# IF1001.net
KiCad netlist of a schematic drawn in Altium Designer
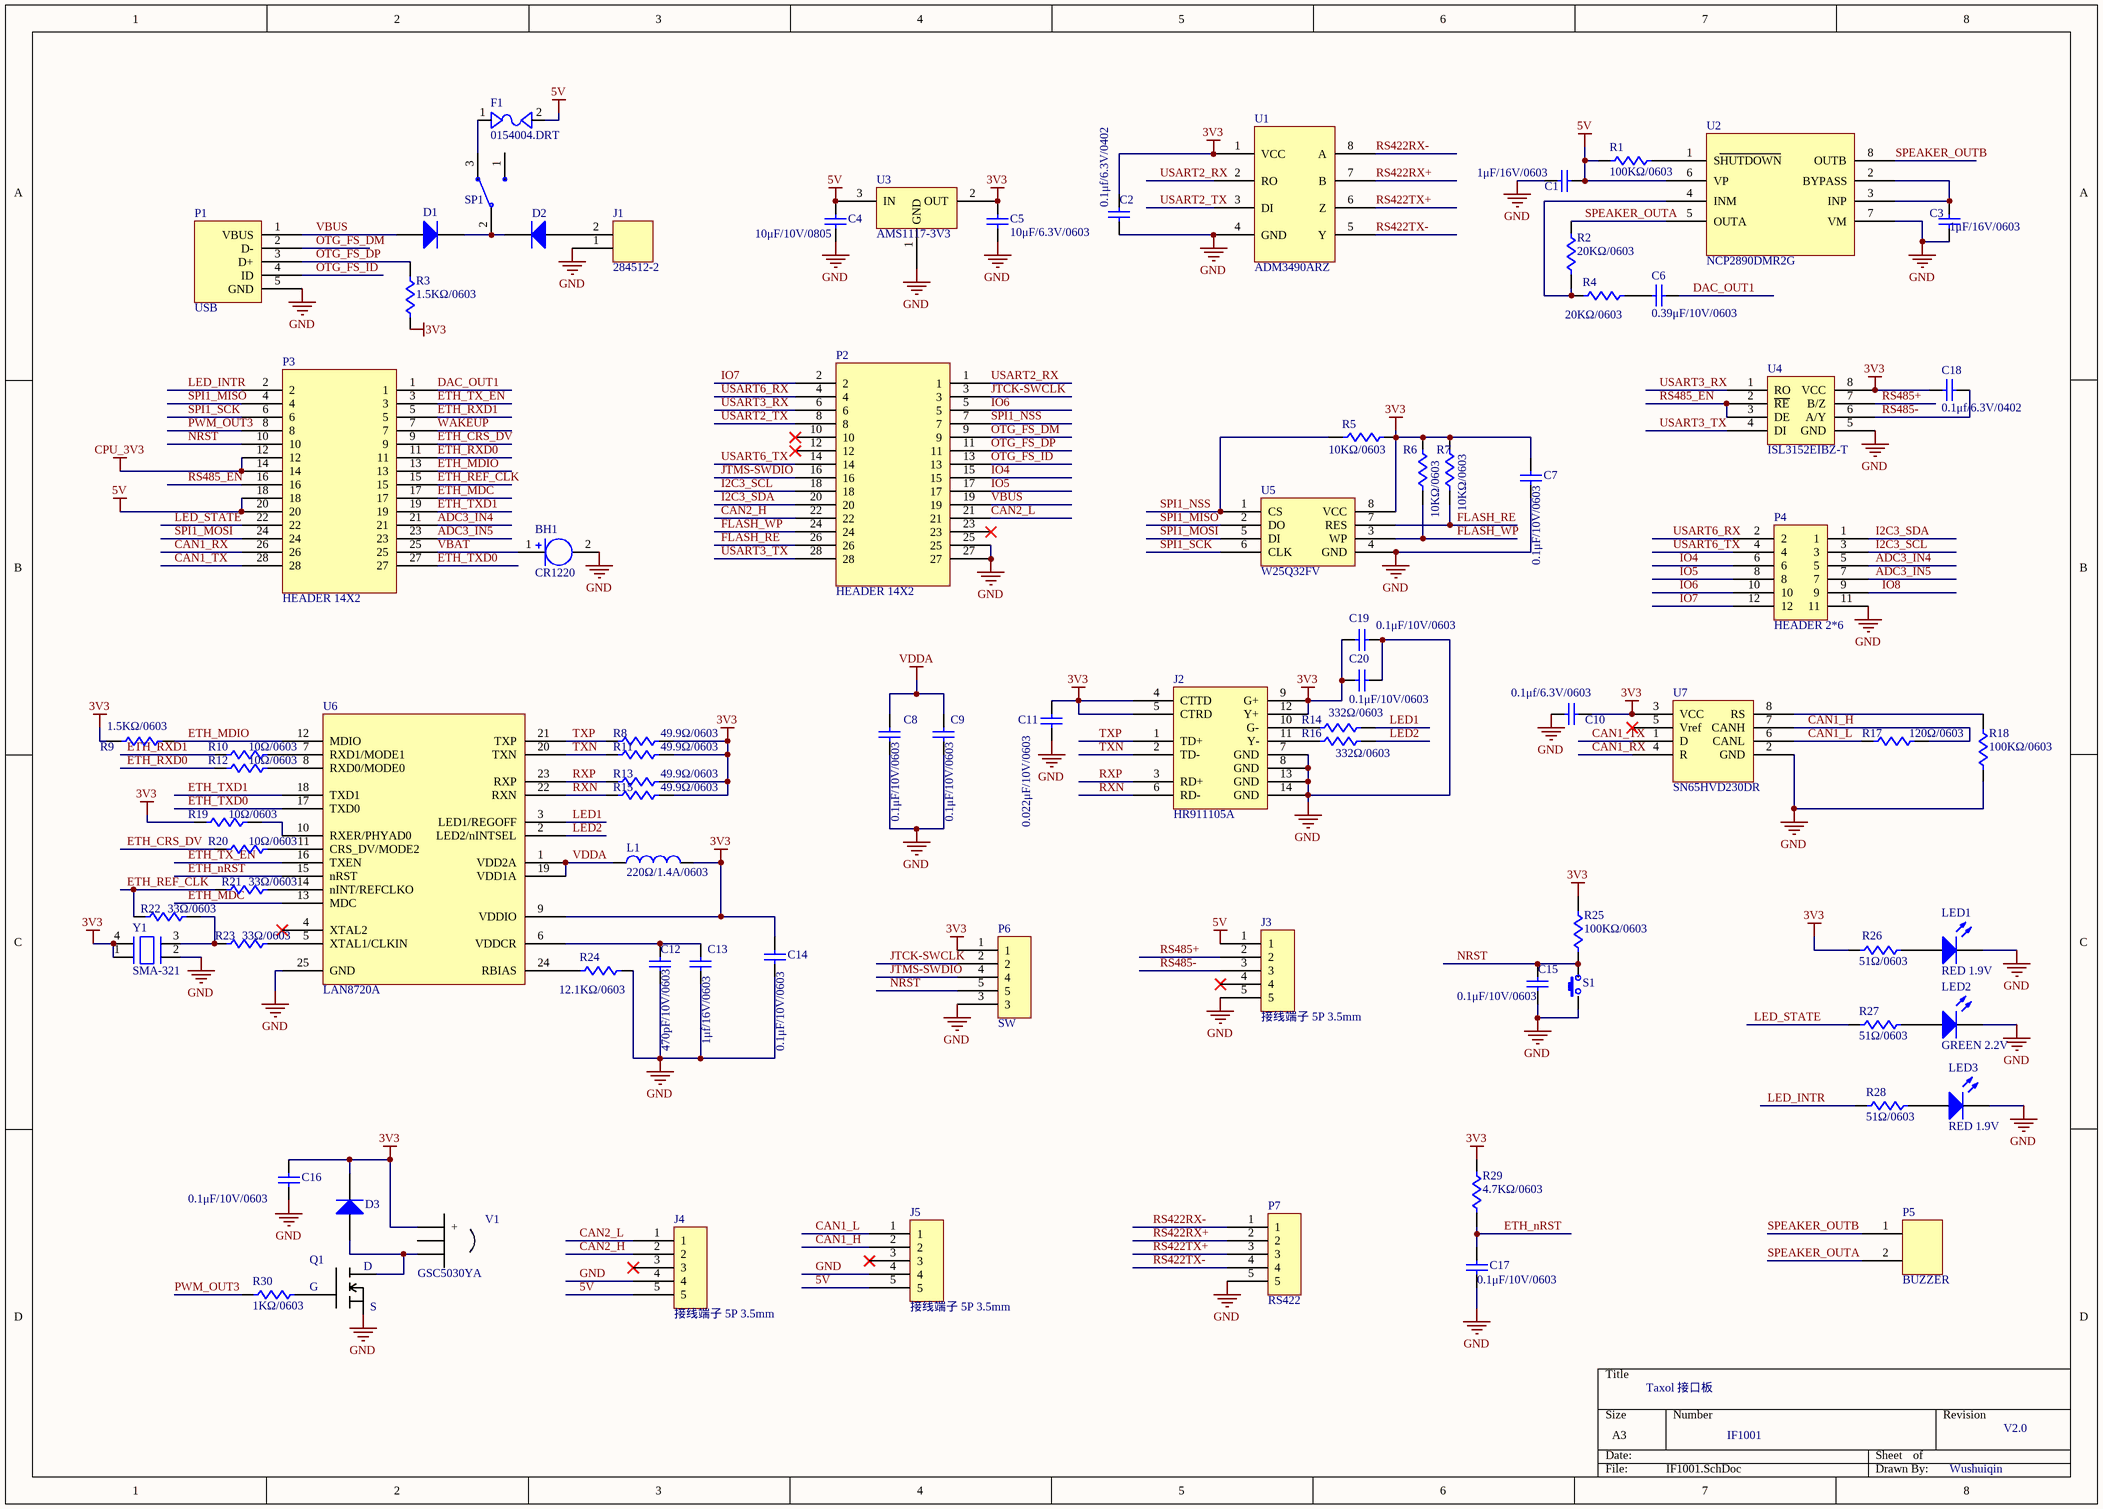
[diagram p0: IF1001.SchDoc]

(export (version "E")
  (design (tool "Eeschema 10.0.6"))
  (components
    (comp (ref "BH1")
      (value "CR1220")
      (footprint "CR1220")
      (fields (field (name "MANUFACTURER") "深圳市吉特雅电子有限公司"))
      (libsource (lib "IF1001") (part "CR1220电池座"))
    )
    (comp (ref "C1")
      (value "1μF/16V/0603")
      (footprint "CAPACITOR_0603")
      (fields (field (name "MANUFACTURER") "TDK"))
      (libsource (lib "Taxol") (part "CAPACITOR_0603"))
    )
    (comp (ref "C2")
      (value "0.1μf/6.3V/0402")
      (footprint "CAPACITOR_0402")
      (fields (field (name "MANUFACTURER") "TDK"))
      (libsource (lib "Taxol") (part "CAPACITOR_0603"))
    )
    (comp (ref "C3")
      (value "1μF/16V/0603")
      (footprint "CAPACITOR_0603")
      (fields (field (name "MANUFACTURER") "TDK"))
      (libsource (lib "Taxol") (part "CAPACITOR_0603"))
    )
    (comp (ref "C4")
      (value "10μF/10V/0805")
      (footprint "CAPACITOR_0805")
      (description "陶瓷电容")
      (fields (field (name "MANUFACTURER") "TDK"))
      (libsource (lib "IF1005") (part "CAP0805 UP"))
    )
    (comp (ref "C5")
      (value "10μF/6.3V/0603")
      (footprint "CAPACITOR_0603")
      (description "陶瓷电容")
      (fields (field (name "MANUFACTURER") "TDK"))
      (libsource (lib "IF1005") (part "CAP0603 UP"))
    )
    (comp (ref "C6")
      (value "0.39μF/10V/0603")
      (footprint "CAPACITOR_0603")
      (fields (field (name "MANUFACTURER") "kemet"))
      (libsource (lib "Taxol") (part "CAPACITOR_0603"))
    )
    (comp (ref "C7")
      (value "0.1μF/10V/0603")
      (footprint "CAPACITOR_0603")
      (fields (field (name "MANUFACTURER") "Vishay"))
      (libsource (lib "Taxol") (part "CAPACITOR_0603"))
    )
    (comp (ref "C8")
      (value "0.1μF/10V/0603")
      (footprint "CAPACITOR_0603")
      (fields (field (name "MANUFACTURER") "Vishay"))
      (libsource (lib "Taxol") (part "CAPACITOR_0603"))
    )
    (comp (ref "C9")
      (value "0.1μF/10V/0603")
      (footprint "CAPACITOR_0603")
      (fields (field (name "MANUFACTURER") "Vishay"))
      (libsource (lib "Taxol") (part "CAPACITOR_0603"))
    )
    (comp (ref "C10")
      (value "0.1μf/6.3V/0603")
      (footprint "CAPACITOR_0603")
      (fields (field (name "MANUFACTURER") "TDK"))
      (libsource (lib "Taxol") (part "CAPACITOR_0603"))
    )
    (comp (ref "C11")
      (value "0.022μF/10V/0603")
      (footprint "CAPACITOR_0603")
      (fields (field (name "MANUFACTURER") "Vishay"))
      (libsource (lib "IF1001") (part "CAPACITOR_0603"))
    )
    (comp (ref "C12")
      (value "470pF/10V/0603")
      (footprint "CAPACITOR_0603")
      (fields (field (name "MANUFACTURER") "Vishay"))
      (libsource (lib "IF1001") (part "CAPACITOR_0603"))
    )
    (comp (ref "C13")
      (value "1μf/16V/0603")
      (footprint "CAPACITOR_0603")
      (fields (field (name "MANUFACTURER") "TDK"))
      (libsource (lib "Taxol") (part "CAPACITOR_0603"))
    )
    (comp (ref "C14")
      (value "0.1μF/10V/0603")
      (footprint "CAPACITOR_0603")
      (fields (field (name "MANUFACTURER") "Vishay"))
      (libsource (lib "Taxol") (part "CAPACITOR_0603"))
    )
    (comp (ref "C15")
      (value "0.1μF/10V/0603")
      (footprint "CAPACITOR_0603")
      (fields (field (name "MANUFACTURER") "Vishay"))
      (libsource (lib "Taxol") (part "CAPACITOR_0603"))
    )
    (comp (ref "C16")
      (value "0.1μF/10V/0603")
      (footprint "CAPACITOR_0603")
      (fields (field (name "MANUFACTURER") "Vishay"))
      (libsource (lib "Taxol") (part "CAPACITOR_0603"))
    )
    (comp (ref "C17")
      (value "0.1μF/10V/0603")
      (footprint "CAPACITOR_0603")
      (fields (field (name "MANUFACTURER") "Vishay"))
      (libsource (lib "Taxol") (part "CAPACITOR_0603"))
    )
    (comp (ref "C18")
      (value "0.1μf/6.3V/0402")
      (footprint "CAPACITOR_0402")
      (fields (field (name "MANUFACTURER") "TDK"))
      (libsource (lib "Taxol") (part "CAPACITOR_0603"))
    )
    (comp (ref "C19")
      (value "0.1μF/10V/0603")
      (footprint "CAPACITOR_0603")
      (fields (field (name "MANUFACTURER") "Vishay"))
      (libsource (lib "Taxol") (part "CAPACITOR_0603"))
    )
    (comp (ref "C20")
      (value "0.1μF/10V/0603")
      (footprint "CAPACITOR_0603")
      (fields (field (name "MANUFACTURER") "Vishay"))
      (libsource (lib "Taxol") (part "CAPACITOR_0603"))
    )
    (comp (ref "D1")
      (value "BAT60JFILM")
      (footprint "BAT60JFILM")
      (fields (field (name "MANUFACTURER") "ST"))
      (libsource (lib "IF1001") (part "BAT60JFILM"))
    )
    (comp (ref "D2")
      (value "BAT60JFILM")
      (footprint "BAT60JFILM")
      (fields (field (name "MANUFACTURER") "ST"))
      (libsource (lib "IF1001") (part "BAT60JFILM"))
    )
    (comp (ref "D3")
      (value "PMEG2010AEB")
      (footprint "PMEG2010AEB_SOD523")
      (fields (field (name "MANUFACTURER") "NXP"))
      (libsource (lib "IF1001") (part "PMEG2010AEB"))
    )
    (comp (ref "F1")
      (value "0154004.DRT")
      (footprint "FUSE1808")
      (description "保险丝")
      (fields (field (name "MANUFACTURER") "Littlefuse"))
      (libsource (lib "IF1001") (part "F_4A"))
    )
    (comp (ref "J1")
      (value "284512-2")
      (footprint "284512-2")
      (description "间距3.5mm")
      (fields (field (name "MANUFACTURER") "TE"))
      (libsource (lib "IF1001") (part "接线端子 2P 3.5mm"))
    )
    (comp (ref "J2")
      (value "HR911105A")
      (footprint "HR911105A")
      (fields (field (name "MANUFACTURER") "深圳市诚亨泰科技有限公司"))
      (libsource (lib "IF1001") (part "HR911105A"))
    )
    (comp (ref "J3")
      (value "接线端子 5P 3.5mm")
      (footprint "接线端子5P 3.5mm")
      (fields (field (name "MANUFACTURER") "KEFA"))
      (libsource (lib "IF1001") (part "接线端子 5P 3.5mm"))
    )
    (comp (ref "J4")
      (value "接线端子 5P 3.5mm")
      (footprint "接线端子5P 3.5mm")
      (fields (field (name "MANUFACTURER") "KEFA"))
      (libsource (lib "IF1001") (part "接线端子 5P 3.5mm"))
    )
    (comp (ref "J5")
      (value "接线端子 5P 3.5mm")
      (footprint "接线端子5P 3.5mm")
      (fields (field (name "MANUFACTURER") "KEFA"))
      (libsource (lib "IF1001") (part "接线端子 5P 3.5mm"))
    )
    (comp (ref "L1")
      (value "220Ω/1.4A/0603")
      (footprint "LNDUCTOR 0603")
      (description "磁珠")
      (fields (field (name "MANUFACTURER") "Murata"))
      (libsource (lib "IF1001") (part "BLM18PG221SN1D"))
    )
    (comp (ref "LED1")
      (value "RED 1.9V")
      (footprint "LED")
      (description "LED_G")
      (fields (field (name "MANUFACTURER") "OSRAM"))
      (libsource (lib "IF1001") (part "LED"))
    )
    (comp (ref "LED2")
      (value "GREEN 2.2V")
      (footprint "LED")
      (description "LED_G")
      (fields (field (name "MANUFACTURER") "OSRAM"))
      (libsource (lib "IF1001") (part "LED"))
    )
    (comp (ref "LED3")
      (value "RED 1.9V")
      (footprint "LED")
      (description "LED_G")
      (fields (field (name "MANUFACTURER") "OSRAM"))
      (libsource (lib "IF1001") (part "LED"))
    )
    (comp (ref "P1")
      (value "USB")
      (footprint "MINI_USB")
      (fields (field (name "MANUFACTURER") "JAE"))
      (libsource (lib "Taxol") (part "Mini_USB"))
    )
    (comp (ref "P2") (value "HEADER 14X2") (footprint "PIN") (libsource (lib "PT1003") (part "PIN_1")))
    (comp (ref "P3") (value "HEADER 14X2") (footprint "PIN") (libsource (lib "PT1003") (part "PIN_1")))
    (comp (ref "P4")
      (value "HEADER 2*6")
      (footprint "HEADER 2*6")
      (libsource (lib "IF1001") (part "HEADER 2*6"))
    )
    (comp (ref "P5") (value "BUZZER") (footprint "HEADER 1*2") (libsource (lib "Taxol") (part "HEADER 1*2")))
    (comp (ref "P6") (value "SW") (footprint "HEADER 1*5") (libsource (lib "Taxol") (part "SW")))
    (comp (ref "P7") (value "RS422") (footprint "HEADER 1*5") (libsource (lib "IF1001") (part "HEADER 1*5")))
    (comp (ref "Q1")
      (value "PMV185XN")
      (footprint "PMV185XN")
      (fields (field (name "MANUFACTURER") "NXP"))
      (libsource (lib "Taxol") (part "MOSFET"))
    )
    (comp (ref "R1")
      (value "100KΩ/0603")
      (footprint "RESSOSTANCE_0603")
      (fields (field (name "MANUFACTURER") "VISHAY"))
      (libsource (lib "Taxol") (part "RESISTANCE"))
    )
    (comp (ref "R2")
      (value "20KΩ/0603")
      (footprint "RESSOSTANCE_0603")
      (fields (field (name "MANUFACTURER") "VISHAY"))
      (libsource (lib "Taxol") (part "RESISTANCE"))
    )
    (comp (ref "R3")
      (value "1.5KΩ/0603")
      (footprint "RESSOSTANCE_0603")
      (fields (field (name "MANUFACTURER") "VISHAY"))
      (libsource (lib "Taxol") (part "RESISTANCE"))
    )
    (comp (ref "R4")
      (value "20KΩ/0603")
      (footprint "RESSOSTANCE_0603")
      (fields (field (name "MANUFACTURER") "VISHAY"))
      (libsource (lib "Taxol") (part "RESISTANCE"))
    )
    (comp (ref "R5")
      (value "10KΩ/0603")
      (footprint "RESSOSTANCE_0603")
      (fields (field (name "MANUFACTURER") "KOA Speer"))
      (libsource (lib "IF1001") (part "RESISTANCE"))
    )
    (comp (ref "R6")
      (value "10KΩ/0603")
      (footprint "RESSOSTANCE_0603")
      (fields (field (name "MANUFACTURER") "KOA Speer"))
      (libsource (lib "IF1001") (part "RESISTANCE"))
    )
    (comp (ref "R7")
      (value "10KΩ/0603")
      (footprint "RESSOSTANCE_0603")
      (fields (field (name "MANUFACTURER") "KOA Speer"))
      (libsource (lib "IF1001") (part "RESISTANCE"))
    )
    (comp (ref "R8")
      (value "49.9Ω/0603")
      (footprint "RESSOSTANCE_0603")
      (fields (field (name "MANUFACTURER") "Vishay"))
      (libsource (lib "IF1001") (part "RESISTANCE"))
    )
    (comp (ref "R9")
      (value "1.5KΩ/0603")
      (footprint "RESSOSTANCE_0603")
      (fields (field (name "MANUFACTURER") "VISHAY"))
      (libsource (lib "Taxol") (part "RESISTANCE"))
    )
    (comp (ref "R10")
      (value "10Ω/0603")
      (footprint "RESSOSTANCE_0603")
      (fields (field (name "MANUFACTURER") "Vishay"))
      (libsource (lib "IF1001") (part "RESISTANCE"))
    )
    (comp (ref "R11")
      (value "49.9Ω/0603")
      (footprint "RESSOSTANCE_0603")
      (fields (field (name "MANUFACTURER") "Vishay"))
      (libsource (lib "IF1001") (part "RESISTANCE"))
    )
    (comp (ref "R12")
      (value "10Ω/0603")
      (footprint "RESSOSTANCE_0603")
      (fields (field (name "MANUFACTURER") "Vishay"))
      (libsource (lib "IF1001") (part "RESISTANCE"))
    )
    (comp (ref "R13")
      (value "49.9Ω/0603")
      (footprint "RESSOSTANCE_0603")
      (fields (field (name "MANUFACTURER") "Vishay"))
      (libsource (lib "IF1001") (part "RESISTANCE"))
    )
    (comp (ref "R14")
      (value "332Ω/0603")
      (footprint "RESSOSTANCE_0603")
      (fields (field (name "MANUFACTURER") "Vishay"))
      (libsource (lib "IF1001") (part "RESISTANCE"))
    )
    (comp (ref "R15")
      (value "49.9Ω/0603")
      (footprint "RESSOSTANCE_0603")
      (fields (field (name "MANUFACTURER") "Vishay"))
      (libsource (lib "IF1001") (part "RESISTANCE"))
    )
    (comp (ref "R16")
      (value "332Ω/0603")
      (footprint "RESSOSTANCE_0603")
      (fields (field (name "MANUFACTURER") "Vishay"))
      (libsource (lib "IF1001") (part "RESISTANCE"))
    )
    (comp (ref "R17")
      (value "120Ω/0603")
      (footprint "RESSOSTANCE_0603")
      (fields (field (name "MANUFACTURER") "Vishay"))
      (libsource (lib "PT1003") (part "RESISTANCE"))
    )
    (comp (ref "R18")
      (value "100KΩ/0603")
      (footprint "RESSOSTANCE_0603")
      (fields (field (name "MANUFACTURER") "VISHAY"))
      (libsource (lib "Taxol") (part "RESISTANCE"))
    )
    (comp (ref "R19")
      (value "10Ω/0603")
      (footprint "RESSOSTANCE_0603")
      (fields (field (name "MANUFACTURER") "Vishay"))
      (libsource (lib "IF1001") (part "RESISTANCE"))
    )
    (comp (ref "R20")
      (value "10Ω/0603")
      (footprint "RESSOSTANCE_0603")
      (fields (field (name "MANUFACTURER") "Vishay"))
      (libsource (lib "IF1001") (part "RESISTANCE"))
    )
    (comp (ref "R21")
      (value "33Ω/0603")
      (footprint "RESSOSTANCE_0603")
      (fields (field (name "MANUFACTURER") "Vishay"))
      (libsource (lib "IF1001") (part "RESISTANCE"))
    )
    (comp (ref "R22")
      (value "33Ω/0603")
      (footprint "RESSOSTANCE_0603")
      (fields (field (name "MANUFACTURER") "Vishay"))
      (libsource (lib "IF1001") (part "RESISTANCE"))
    )
    (comp (ref "R23")
      (value "33Ω/0603")
      (footprint "RESSOSTANCE_0603")
      (fields (field (name "MANUFACTURER") "Vishay"))
      (libsource (lib "IF1001") (part "RESISTANCE"))
    )
    (comp (ref "R24")
      (value "12.1KΩ/0603")
      (footprint "RESSOSTANCE_0603")
      (fields (field (name "MANUFACTURER") "Vishay"))
      (libsource (lib "IF1001") (part "RESISTANCE"))
    )
    (comp (ref "R25")
      (value "100KΩ/0603")
      (footprint "RESSOSTANCE_0603")
      (fields (field (name "MANUFACTURER") "VISHAY"))
      (libsource (lib "Taxol") (part "RESISTANCE"))
    )
    (comp (ref "R26")
      (value "51Ω/0603")
      (footprint "RESSOSTANCE_0603")
      (fields (field (name "MANUFACTURER") "Vishay"))
      (libsource (lib "IF1001") (part "RESISTANCE"))
    )
    (comp (ref "R27")
      (value "51Ω/0603")
      (footprint "RESSOSTANCE_0603")
      (fields (field (name "MANUFACTURER") "Vishay"))
      (libsource (lib "IF1001") (part "RESISTANCE"))
    )
    (comp (ref "R28")
      (value "51Ω/0603")
      (footprint "RESSOSTANCE_0603")
      (fields (field (name "MANUFACTURER") "Vishay"))
      (libsource (lib "IF1001") (part "RESISTANCE"))
    )
    (comp (ref "R29")
      (value "4.7KΩ/0603")
      (footprint "RESSOSTANCE_0603")
      (fields (field (name "MANUFACTURER") "Vishay"))
      (libsource (lib "IF1001") (part "RESISTANCE"))
    )
    (comp (ref "R30")
      (value "1KΩ/0603")
      (footprint "RESSOSTANCE_0603")
      (fields (field (name "MANUFACTURER") "VISHAY"))
      (libsource (lib "Taxol") (part "RESISTANCE"))
    )
    (comp (ref "S1")
      (value "K2-1107ST")
      (footprint "SW-侧开")
      (fields (field (name "MANUFACTURER") "韩荣"))
      (libsource (lib "Taxol") (part "SW_PB"))
    )
    (comp (ref "SP1")
      (value "2.00mm 3P SPDT")
      (footprint "SW-STDP")
      (libsource (lib "Taxol") (part "SW_STDP"))
    )
    (comp (ref "U1")
      (value "ADM3490ARZ")
      (footprint "ADM3490")
      (description "RS422")
      (fields (field (name "MANUFACTURER") "ANALOG DEVICES"))
      (libsource (lib "Taxol") (part "ADM3490ARZ"))
    )
    (comp (ref "U2")
      (value "NCP2890DMR2G")
      (footprint "NCP2890")
      (description "AUDIO")
      (fields (field (name "MANUFACTURER") "ON"))
      (libsource (lib "Taxol") (part "NCP2890DMR2G"))
    )
    (comp (ref "U3")
      (value "AMS1117-3V3")
      (footprint "AMS1117-3V3")
      (description "3V3稳压芯片")
      (fields (field (name "MANUFACTURER") "Advanced Monolithic Systems"))
      (libsource (lib "IF1005") (part "AMS1117-3V3"))
    )
    (comp (ref "U4")
      (value "ISL3152EIBZ-T")
      (footprint "ISL3152EIBZ-T")
      (description "RS485接口芯片")
      (fields (field (name "MANUFACTURER") "INTERSIL"))
      (libsource (lib "IF1001") (part "ISL3152EIBZ-T"))
    )
    (comp (ref "U5")
      (value "W25Q32FV")
      (footprint "W25Q32FV")
      (fields (field (name "MANUFACTURER") "华邦电子"))
      (libsource (lib "IF1001") (part "W25Q32FV"))
    )
    (comp (ref "U6")
      (value "LAN8720A")
      (footprint "LAN8720A")
      (fields (field (name "MANUFACTURER") "SMSC"))
      (libsource (lib "IF1001") (part "LAN8720A"))
    )
    (comp (ref "U7")
      (value "SN65HVD230DR")
      (footprint "SN65HVD230")
      (description "CAN")
      (fields (field (name "MANUFACTURER") "TEXAS INSTRUMENTS"))
      (libsource (lib "Taxol") (part "SN65HVD230DR"))
    )
    (comp (ref "V1")
      (value "GSC5030YA")
      (footprint "GSC5030YA-12R4000")
      (fields (field (name "MANUFACTURER") "INGHAI"))
      (libsource (lib "Taxol") (part "BUZZER"))
    )
    (comp (ref "Y1")
      (value "SMA-321")
      (footprint "XO35")
      (description "有源晶振")
      (fields (field (name "MANUFACTURER") "AKER"))
      (libsource (lib "IF1001") (part "SMA-321"))
    )
  )
  (nets
    (net (code "1") (name "/ADC3_IN4") (class "Default")
      (node (ref "P3") (pin "21") (pinfunction "21_21") (pintype "passive"))
      (node (ref "P4") (pin "5") (pinfunction "5_5") (pintype "passive"))
    )
    (net (code "2") (name "/ADC3_IN5") (class "Default")
      (node (ref "P3") (pin "23") (pinfunction "23_23") (pintype "passive"))
      (node (ref "P4") (pin "7") (pinfunction "7_7") (pintype "passive"))
    )
    (net (code "3") (name "/CAN1_H") (class "Default")
      (node (ref "J5") (pin "2") (pinfunction "2_2") (pintype "passive"))
      (node (ref "R17") (pin "2") (pinfunction "2_2") (pintype "passive"))
      (node (ref "U7") (pin "7") (pinfunction "CANH_7") (pintype "passive"))
    )
    (net (code "4") (name "/CAN1_L") (class "Default")
      (node (ref "J5") (pin "1") (pinfunction "1_1") (pintype "passive"))
      (node (ref "R17") (pin "1") (pinfunction "1_1") (pintype "passive"))
      (node (ref "U7") (pin "6") (pinfunction "CANL_6") (pintype "passive"))
    )
    (net (code "5") (name "/CAN1_RX") (class "Default")
      (node (ref "P3") (pin "26") (pinfunction "26_26") (pintype "passive"))
      (node (ref "U7") (pin "4") (pinfunction "R_4") (pintype "passive"))
    )
    (net (code "6") (name "/CAN1_TX") (class "Default")
      (node (ref "P3") (pin "28") (pinfunction "28_28") (pintype "passive"))
      (node (ref "U7") (pin "1") (pinfunction "D_1") (pintype "passive"))
    )
    (net (code "7") (name "/CAN2_H") (class "Default")
      (node (ref "J4") (pin "2") (pinfunction "2_2") (pintype "passive"))
      (node (ref "P2") (pin "22") (pinfunction "22_22") (pintype "passive"))
    )
    (net (code "8") (name "/CAN2_L") (class "Default")
      (node (ref "J4") (pin "1") (pinfunction "1_1") (pintype "passive"))
      (node (ref "P2") (pin "21") (pinfunction "21_21") (pintype "passive"))
    )
    (net (code "9") (name "/DAC_OUT1") (class "Default")
      (node (ref "C6") (pin "2") (pinfunction "2_2") (pintype "passive"))
      (node (ref "P3") (pin "1") (pinfunction "1_1") (pintype "passive"))
    )
    (net (code "10") (name "/ETH_CRS_DV") (class "Default")
      (node (ref "P3") (pin "9") (pinfunction "9_9") (pintype "passive"))
      (node (ref "R20") (pin "1") (pinfunction "1_1") (pintype "passive"))
    )
    (net (code "11") (name "/ETH_MDC") (class "Default")
      (node (ref "P3") (pin "17") (pinfunction "17_17") (pintype "passive"))
      (node (ref "U6") (pin "13") (pinfunction "MDC_13") (pintype "passive"))
    )
    (net (code "12") (name "/ETH_MDIO") (class "Default")
      (node (ref "P3") (pin "13") (pinfunction "13_13") (pintype "passive"))
      (node (ref "R9") (pin "1") (pinfunction "1_1") (pintype "passive"))
      (node (ref "U6") (pin "12") (pinfunction "MDIO_12") (pintype "passive"))
    )
    (net (code "13") (name "/ETH_REF_CLK") (class "Default")
      (node (ref "P3") (pin "15") (pinfunction "15_15") (pintype "passive"))
      (node (ref "R21") (pin "1") (pinfunction "1_1") (pintype "passive"))
      (node (ref "R22") (pin "1") (pinfunction "1_1") (pintype "passive"))
    )
    (net (code "14") (name "/ETH_RXD0") (class "Default")
      (node (ref "P3") (pin "11") (pinfunction "11_11") (pintype "passive"))
      (node (ref "R12") (pin "1") (pinfunction "1_1") (pintype "passive"))
    )
    (net (code "15") (name "/ETH_RXD1") (class "Default")
      (node (ref "P3") (pin "5") (pinfunction "5_5") (pintype "passive"))
      (node (ref "R10") (pin "1") (pinfunction "1_1") (pintype "passive"))
    )
    (net (code "16") (name "/ETH_TXD0") (class "Default")
      (node (ref "P3") (pin "27") (pinfunction "27_27") (pintype "passive"))
      (node (ref "U6") (pin "17") (pinfunction "TXD0_17") (pintype "passive"))
    )
    (net (code "17") (name "/ETH_TXD1") (class "Default")
      (node (ref "P3") (pin "19") (pinfunction "19_19") (pintype "passive"))
      (node (ref "U6") (pin "18") (pinfunction "TXD1_18") (pintype "passive"))
    )
    (net (code "18") (name "/ETH_TX_EN") (class "Default")
      (node (ref "P3") (pin "3") (pinfunction "3_3") (pintype "passive"))
      (node (ref "U6") (pin "16") (pinfunction "TXEN_16") (pintype "passive"))
    )
    (net (code "19") (name "/ETH_nRST") (class "Default")
      (node (ref "C17") (pin "2") (pinfunction "2_2") (pintype "passive"))
      (node (ref "R29") (pin "2") (pinfunction "2_2") (pintype "passive"))
      (node (ref "U6") (pin "15") (pinfunction "nRST_15") (pintype "passive"))
    )
    (net (code "20") (name "/FLASH_RE") (class "Default")
      (node (ref "P2") (pin "26") (pinfunction "26_26") (pintype "passive"))
      (node (ref "R7") (pin "2") (pinfunction "2_2") (pintype "passive"))
      (node (ref "U5") (pin "7") (pinfunction "RES_7") (pintype "passive"))
    )
    (net (code "21") (name "/FLASH_WP") (class "Default")
      (node (ref "P2") (pin "24") (pinfunction "24_24") (pintype "passive"))
      (node (ref "R6") (pin "2") (pinfunction "2_2") (pintype "passive"))
      (node (ref "U5") (pin "3") (pinfunction "WP_3") (pintype "passive"))
    )
    (net (code "22") (name "/I2C3_SCL") (class "Default")
      (node (ref "P2") (pin "18") (pinfunction "18_18") (pintype "passive"))
      (node (ref "P4") (pin "3") (pinfunction "3_3") (pintype "passive"))
    )
    (net (code "23") (name "/I2C3_SDA") (class "Default")
      (node (ref "P2") (pin "20") (pinfunction "20_20") (pintype "passive"))
      (node (ref "P4") (pin "1") (pinfunction "1_1") (pintype "passive"))
    )
    (net (code "24") (name "/IO4") (class "Default")
      (node (ref "P2") (pin "15") (pinfunction "15_15") (pintype "passive"))
      (node (ref "P4") (pin "6") (pinfunction "6_6") (pintype "passive"))
    )
    (net (code "25") (name "/IO5") (class "Default")
      (node (ref "P2") (pin "17") (pinfunction "17_17") (pintype "passive"))
      (node (ref "P4") (pin "8") (pinfunction "8_8") (pintype "passive"))
    )
    (net (code "26") (name "/IO6") (class "Default")
      (node (ref "P2") (pin "5") (pinfunction "5_5") (pintype "passive"))
      (node (ref "P4") (pin "10") (pinfunction "10_10") (pintype "passive"))
    )
    (net (code "27") (name "/IO7") (class "Default")
      (node (ref "P2") (pin "2") (pinfunction "2_2") (pintype "passive"))
      (node (ref "P4") (pin "12") (pinfunction "12_12") (pintype "passive"))
    )
    (net (code "28") (name "/IO8") (class "Default")
      (node (ref "P4") (pin "9") (pinfunction "9_9") (pintype "passive"))
    )
    (net (code "29") (name "/JTCK-SWCLK") (class "Default")
      (node (ref "P2") (pin "3") (pinfunction "3_3") (pintype "passive"))
      (node (ref "P6") (pin "2") (pinfunction "2_2") (pintype "passive"))
    )
    (net (code "30") (name "/JTMS-SWDIO") (class "Default")
      (node (ref "P2") (pin "16") (pinfunction "16_16") (pintype "passive"))
      (node (ref "P6") (pin "4") (pinfunction "4_4") (pintype "passive"))
    )
    (net (code "31") (name "/LED1") (class "Default")
      (node (ref "R14") (pin "2") (pinfunction "2_2") (pintype "passive"))
      (node (ref "U6") (pin "3") (pinfunction "LED1/REGOFF_3") (pintype "passive"))
    )
    (net (code "32") (name "/LED2") (class "Default")
      (node (ref "R16") (pin "2") (pinfunction "2_2") (pintype "passive"))
      (node (ref "U6") (pin "2") (pinfunction "LED2/nINTSEL_2") (pintype "passive"))
    )
    (net (code "33") (name "/LED_INTR") (class "Default")
      (node (ref "P3") (pin "2") (pinfunction "2_2") (pintype "passive"))
      (node (ref "R28") (pin "1") (pinfunction "1_1") (pintype "passive"))
    )
    (net (code "34") (name "/LED_STATE") (class "Default")
      (node (ref "P3") (pin "22") (pinfunction "22_22") (pintype "passive"))
      (node (ref "R27") (pin "1") (pinfunction "1_1") (pintype "passive"))
    )
    (net (code "35") (name "/NRST") (class "Default")
      (node (ref "C15") (pin "2") (pinfunction "2_2") (pintype "passive"))
      (node (ref "P3") (pin "10") (pinfunction "10_10") (pintype "passive"))
      (node (ref "P6") (pin "5") (pinfunction "5_5") (pintype "passive"))
      (node (ref "R25") (pin "1") (pinfunction "1_1") (pintype "passive"))
      (node (ref "S1") (pin "2") (pinfunction "2_2") (pintype "passive"))
    )
    (net (code "36") (name "/OTG_FS_DM") (class "Default")
      (node (ref "P1") (pin "2") (pinfunction "D-_2") (pintype "passive"))
      (node (ref "P2") (pin "9") (pinfunction "9_9") (pintype "passive"))
    )
    (net (code "37") (name "/OTG_FS_DP") (class "Default")
      (node (ref "P1") (pin "3") (pinfunction "D+_3") (pintype "passive"))
      (node (ref "P2") (pin "11") (pinfunction "11_11") (pintype "passive"))
      (node (ref "R3") (pin "2") (pinfunction "2_2") (pintype "passive"))
    )
    (net (code "38") (name "/OTG_FS_ID") (class "Default")
      (node (ref "P1") (pin "4") (pinfunction "ID_4") (pintype "passive"))
      (node (ref "P2") (pin "13") (pinfunction "13_13") (pintype "passive"))
    )
    (net (code "39") (name "/PWM_OUT3") (class "Default")
      (node (ref "P3") (pin "8") (pinfunction "8_8") (pintype "passive"))
      (node (ref "R30") (pin "1") (pinfunction "1_1") (pintype "passive"))
    )
    (net (code "40") (name "/RS422RX+") (class "Default")
      (node (ref "P7") (pin "2") (pinfunction "2_2") (pintype "passive"))
      (node (ref "U1") (pin "7") (pinfunction "B_7") (pintype "passive"))
    )
    (net (code "41") (name "/RS422RX-") (class "Default")
      (node (ref "P7") (pin "1") (pinfunction "1_1") (pintype "passive"))
      (node (ref "U1") (pin "8") (pinfunction "A_8") (pintype "passive"))
    )
    (net (code "42") (name "/RS422TX+") (class "Default")
      (node (ref "P7") (pin "3") (pinfunction "3_3") (pintype "passive"))
      (node (ref "U1") (pin "6") (pinfunction "Z_6") (pintype "passive"))
    )
    (net (code "43") (name "/RS422TX-") (class "Default")
      (node (ref "P7") (pin "4") (pinfunction "4_4") (pintype "passive"))
      (node (ref "U1") (pin "5") (pinfunction "Y_5") (pintype "passive"))
    )
    (net (code "44") (name "/RS485+") (class "Default")
      (node (ref "J3") (pin "2") (pinfunction "2_2") (pintype "passive"))
      (node (ref "U4") (pin "7") (pinfunction "B/Z_7") (pintype "passive"))
    )
    (net (code "45") (name "/RS485-") (class "Default")
      (node (ref "C18") (pin "1") (pinfunction "1_1") (pintype "passive"))
      (node (ref "J3") (pin "3") (pinfunction "3_3") (pintype "passive"))
      (node (ref "U4") (pin "6") (pinfunction "A/Y_6") (pintype "passive"))
    )
    (net (code "46") (name "/RS485_EN") (class "Default")
      (node (ref "P3") (pin "16") (pinfunction "16_16") (pintype "passive"))
      (node (ref "U4") (pin "2") (pinfunction "~{RE}_2") (pintype "passive"))
      (node (ref "U4") (pin "3") (pinfunction "DE_3") (pintype "passive"))
    )
    (net (code "47") (name "/RXN") (class "Default")
      (node (ref "J2") (pin "6") (pinfunction "RD-_6") (pintype "passive"))
      (node (ref "R15") (pin "1") (pinfunction "1_1") (pintype "passive"))
      (node (ref "U6") (pin "22") (pinfunction "RXN_22") (pintype "passive"))
    )
    (net (code "48") (name "/RXP") (class "Default")
      (node (ref "J2") (pin "3") (pinfunction "RD+_3") (pintype "passive"))
      (node (ref "R13") (pin "1") (pinfunction "1_1") (pintype "passive"))
      (node (ref "U6") (pin "23") (pinfunction "RXP_23") (pintype "passive"))
    )
    (net (code "49") (name "/SPEAKER_OUTA") (class "Default")
      (node (ref "P5") (pin "2") (pintype "passive"))
      (node (ref "R2") (pin "1") (pinfunction "1_1") (pintype "passive"))
      (node (ref "U2") (pin "5") (pinfunction "OUTA_5") (pintype "passive"))
    )
    (net (code "50") (name "/SPEAKER_OUTB") (class "Default")
      (node (ref "P5") (pin "1") (pintype "passive"))
      (node (ref "U2") (pin "8") (pinfunction "OUTB_8") (pintype "passive"))
    )
    (net (code "51") (name "/SPI1_MISO") (class "Default")
      (node (ref "P3") (pin "4") (pinfunction "4_4") (pintype "passive"))
      (node (ref "U5") (pin "2") (pinfunction "DO_2") (pintype "passive"))
    )
    (net (code "52") (name "/SPI1_MOSI") (class "Default")
      (node (ref "P3") (pin "24") (pinfunction "24_24") (pintype "passive"))
      (node (ref "U5") (pin "5") (pinfunction "DI_5") (pintype "passive"))
    )
    (net (code "53") (name "/SPI1_NSS") (class "Default")
      (node (ref "P2") (pin "7") (pinfunction "7_7") (pintype "passive"))
      (node (ref "R5") (pin "2") (pinfunction "2_2") (pintype "passive"))
      (node (ref "U5") (pin "1") (pinfunction "CS_1") (pintype "passive"))
    )
    (net (code "54") (name "/SPI1_SCK") (class "Default")
      (node (ref "P3") (pin "6") (pinfunction "6_6") (pintype "passive"))
      (node (ref "U5") (pin "6") (pinfunction "CLK_6") (pintype "passive"))
    )
    (net (code "55") (name "/TXN") (class "Default")
      (node (ref "J2") (pin "2") (pinfunction "TD-_2") (pintype "passive"))
      (node (ref "R11") (pin "1") (pinfunction "1_1") (pintype "passive"))
      (node (ref "U6") (pin "20") (pinfunction "TXN_20") (pintype "passive"))
    )
    (net (code "56") (name "/TXP") (class "Default")
      (node (ref "J2") (pin "1") (pinfunction "TD+_1") (pintype "passive"))
      (node (ref "R8") (pin "1") (pinfunction "1_1") (pintype "passive"))
      (node (ref "U6") (pin "21") (pinfunction "TXP_21") (pintype "passive"))
    )
    (net (code "57") (name "/USART2_RX") (class "Default")
      (node (ref "P2") (pin "1") (pinfunction "1_1") (pintype "passive"))
      (node (ref "U1") (pin "2") (pinfunction "RO_2") (pintype "passive"))
    )
    (net (code "58") (name "/USART2_TX") (class "Default")
      (node (ref "P2") (pin "8") (pinfunction "8_8") (pintype "passive"))
      (node (ref "U1") (pin "3") (pinfunction "DI_3") (pintype "passive"))
    )
    (net (code "59") (name "/USART3_RX") (class "Default")
      (node (ref "P2") (pin "6") (pinfunction "6_6") (pintype "passive"))
      (node (ref "U4") (pin "1") (pinfunction "RO_1") (pintype "passive"))
    )
    (net (code "60") (name "/USART3_TX") (class "Default")
      (node (ref "P2") (pin "28") (pinfunction "28_28") (pintype "passive"))
      (node (ref "U4") (pin "4") (pinfunction "DI_4") (pintype "passive"))
    )
    (net (code "61") (name "/USART6_RX") (class "Default")
      (node (ref "P2") (pin "4") (pinfunction "4_4") (pintype "passive"))
      (node (ref "P4") (pin "2") (pinfunction "2_2") (pintype "passive"))
    )
    (net (code "62") (name "/USART6_TX") (class "Default")
      (node (ref "P2") (pin "14") (pinfunction "14_14") (pintype "passive"))
      (node (ref "P4") (pin "4") (pinfunction "4_4") (pintype "passive"))
    )
    (net (code "63") (name "/VBAT") (class "Default")
      (node (ref "BH1") (pin "1") (pintype "passive"))
      (node (ref "P3") (pin "25") (pinfunction "25_25") (pintype "passive"))
    )
    (net (code "64") (name "/VBUS") (class "Default")
      (node (ref "D1") (pin "1") (pinfunction "A_1") (pintype "passive"))
      (node (ref "P1") (pin "1") (pinfunction "VBUS_1") (pintype "passive"))
      (node (ref "P2") (pin "19") (pinfunction "19_19") (pintype "passive"))
    )
    (net (code "65") (name "/WAKEUP") (class "Default")
      (node (ref "P3") (pin "7") (pinfunction "7_7") (pintype "passive"))
    )
    (net (code "66") (name "3V3") (class "Default")
      (node (ref "C10") (pin "1") (pinfunction "1_1") (pintype "passive"))
      (node (ref "C11") (pin "2") (pinfunction "2_2") (pintype "passive"))
      (node (ref "C14") (pin "2") (pinfunction "2_2") (pintype "passive"))
      (node (ref "C16") (pin "2") (pinfunction "2_2") (pintype "passive"))
      (node (ref "C18") (pin "2") (pinfunction "2_2") (pintype "passive"))
      (node (ref "C19") (pin "2") (pinfunction "2_2") (pintype "passive"))
      (node (ref "C2") (pin "2") (pinfunction "2_2") (pintype "passive"))
      (node (ref "C20") (pin "2") (pinfunction "2_2") (pintype "passive"))
      (node (ref "C5") (pin "2") (pinfunction "2_2") (pintype "passive"))
      (node (ref "C7") (pin "2") (pinfunction "2_2") (pintype "passive"))
      (node (ref "D3") (pin "2") (pinfunction "K_2") (pintype "passive"))
      (node (ref "J2") (pin "12") (pinfunction "Y+_12") (pintype "passive"))
      (node (ref "J2") (pin "4") (pinfunction "CTTD_4") (pintype "passive"))
      (node (ref "J2") (pin "5") (pinfunction "CTRD_5") (pintype "passive"))
      (node (ref "J2") (pin "9") (pinfunction "G+_9") (pintype "passive"))
      (node (ref "L1") (pin "2") (pinfunction "2_2") (pintype "passive"))
      (node (ref "P6") (pin "1") (pinfunction "1_1") (pintype "passive"))
      (node (ref "R11") (pin "2") (pinfunction "2_2") (pintype "passive"))
      (node (ref "R13") (pin "2") (pinfunction "2_2") (pintype "passive"))
      (node (ref "R15") (pin "2") (pinfunction "2_2") (pintype "passive"))
      (node (ref "R19") (pin "1") (pinfunction "1_1") (pintype "passive"))
      (node (ref "R25") (pin "2") (pinfunction "2_2") (pintype "passive"))
      (node (ref "R26") (pin "1") (pinfunction "1_1") (pintype "passive"))
      (node (ref "R29") (pin "1") (pinfunction "1_1") (pintype "passive"))
      (node (ref "R3") (pin "1") (pinfunction "1_1") (pintype "passive"))
      (node (ref "R5") (pin "1") (pinfunction "1_1") (pintype "passive"))
      (node (ref "R6") (pin "1") (pinfunction "1_1") (pintype "passive"))
      (node (ref "R7") (pin "1") (pinfunction "1_1") (pintype "passive"))
      (node (ref "R8") (pin "2") (pinfunction "2_2") (pintype "passive"))
      (node (ref "R9") (pin "2") (pinfunction "2_2") (pintype "passive"))
      (node (ref "U1") (pin "1") (pinfunction "VCC_1") (pintype "passive"))
      (node (ref "U3") (pin "2") (pinfunction "OUT_2") (pintype "passive"))
      (node (ref "U4") (pin "8") (pinfunction "VCC_8") (pintype "passive"))
      (node (ref "U5") (pin "8") (pinfunction "VCC_8") (pintype "passive"))
      (node (ref "U6") (pin "9") (pinfunction "VDDIO_9") (pintype "passive"))
      (node (ref "U7") (pin "3") (pinfunction "VCC_3") (pintype "passive"))
      (node (ref "V1") (pin "1") (pinfunction "+_1") (pintype "passive"))
      (node (ref "Y1") (pin "1") (pintype "passive"))
      (node (ref "Y1") (pin "4") (pintype "passive"))
    )
    (net (code "67") (name "5V") (class "Default")
      (node (ref "C1") (pin "2") (pinfunction "2_2") (pintype "passive"))
      (node (ref "C4") (pin "2") (pinfunction "2_2") (pintype "passive"))
      (node (ref "F1") (pin "2") (pinfunction "P2_2") (pintype "passive"))
      (node (ref "J3") (pin "1") (pinfunction "1_1") (pintype "passive"))
      (node (ref "J4") (pin "5") (pinfunction "5_5") (pintype "passive"))
      (node (ref "J5") (pin "5") (pinfunction "5_5") (pintype "passive"))
      (node (ref "P3") (pin "18") (pinfunction "18_18") (pintype "passive"))
      (node (ref "P3") (pin "20") (pinfunction "20_20") (pintype "passive"))
      (node (ref "R1") (pin "1") (pinfunction "1_1") (pintype "passive"))
      (node (ref "U2") (pin "6") (pinfunction "VP_6") (pintype "passive"))
      (node (ref "U3") (pin "3") (pinfunction "IN_3") (pintype "passive"))
    )
    (net (code "68") (name "CPU_3V3") (class "Default")
      (node (ref "P3") (pin "12") (pinfunction "12_12") (pintype "passive"))
      (node (ref "P3") (pin "14") (pinfunction "14_14") (pintype "passive"))
    )
    (net (code "69") (name "GND") (class "Default")
      (node (ref "BH1") (pin "2") (pintype "passive"))
      (node (ref "C1") (pin "1") (pinfunction "1_1") (pintype "passive"))
      (node (ref "C10") (pin "2") (pinfunction "2_2") (pintype "passive"))
      (node (ref "C11") (pin "1") (pinfunction "1_1") (pintype "passive"))
      (node (ref "C12") (pin "2") (pinfunction "2_2") (pintype "passive"))
      (node (ref "C13") (pin "2") (pinfunction "2_2") (pintype "passive"))
      (node (ref "C14") (pin "1") (pinfunction "1_1") (pintype "passive"))
      (node (ref "C15") (pin "1") (pinfunction "1_1") (pintype "passive"))
      (node (ref "C16") (pin "1") (pinfunction "1_1") (pintype "passive"))
      (node (ref "C17") (pin "1") (pinfunction "1_1") (pintype "passive"))
      (node (ref "C19") (pin "1") (pinfunction "1_1") (pintype "passive"))
      (node (ref "C2") (pin "1") (pinfunction "1_1") (pintype "passive"))
      (node (ref "C20") (pin "1") (pinfunction "1_1") (pintype "passive"))
      (node (ref "C3") (pin "1") (pinfunction "1_1") (pintype "passive"))
      (node (ref "C4") (pin "1") (pinfunction "1_1") (pintype "passive"))
      (node (ref "C5") (pin "1") (pinfunction "1_1") (pintype "passive"))
      (node (ref "C7") (pin "1") (pinfunction "1_1") (pintype "passive"))
      (node (ref "C8") (pin "1") (pinfunction "1_1") (pintype "passive"))
      (node (ref "C9") (pin "1") (pinfunction "1_1") (pintype "passive"))
      (node (ref "J1") (pin "1") (pintype "passive"))
      (node (ref "J2") (pin "13") (pinfunction "GND_13") (pintype "passive"))
      (node (ref "J2") (pin "14") (pinfunction "GND_14") (pintype "passive"))
      (node (ref "J2") (pin "7") (pinfunction "GND_7") (pintype "passive"))
      (node (ref "J2") (pin "8") (pinfunction "GND_8") (pintype "passive"))
      (node (ref "J3") (pin "5") (pinfunction "5_5") (pintype "passive"))
      (node (ref "J4") (pin "4") (pinfunction "4_4") (pintype "passive"))
      (node (ref "J5") (pin "4") (pinfunction "4_4") (pintype "passive"))
      (node (ref "LED1") (pin "2") (pinfunction "K_2") (pintype "passive"))
      (node (ref "LED2") (pin "2") (pinfunction "K_2") (pintype "passive"))
      (node (ref "LED3") (pin "2") (pinfunction "K_2") (pintype "passive"))
      (node (ref "P1") (pin "5") (pinfunction "GND_5") (pintype "passive"))
      (node (ref "P2") (pin "25") (pinfunction "25_25") (pintype "passive"))
      (node (ref "P2") (pin "27") (pinfunction "27_27") (pintype "passive"))
      (node (ref "P4") (pin "11") (pinfunction "11_11") (pintype "passive"))
      (node (ref "P6") (pin "3") (pinfunction "3_3") (pintype "passive"))
      (node (ref "P7") (pin "5") (pinfunction "5_5") (pintype "passive"))
      (node (ref "Q1") (pin "2") (pinfunction "S_2") (pintype "passive"))
      (node (ref "R18") (pin "1") (pinfunction "1_1") (pintype "passive"))
      (node (ref "R24") (pin "1") (pinfunction "1_1") (pintype "passive"))
      (node (ref "S1") (pin "1") (pinfunction "1_1") (pintype "passive"))
      (node (ref "U1") (pin "4") (pinfunction "GND_4") (pintype "passive"))
      (node (ref "U2") (pin "7") (pinfunction "VM_7") (pintype "passive"))
      (node (ref "U3") (pin "1") (pinfunction "GND_1") (pintype "passive"))
      (node (ref "U4") (pin "5") (pinfunction "GND_5") (pintype "passive"))
      (node (ref "U5") (pin "4") (pinfunction "GND_4") (pintype "passive"))
      (node (ref "U6") (pin "25") (pinfunction "GND_25") (pintype "passive"))
      (node (ref "U7") (pin "2") (pinfunction "GND_2") (pintype "passive"))
      (node (ref "Y1") (pin "2") (pintype "passive"))
    )
    (net (code "70") (name "Net-(C6-Pad1)") (class "Default")
      (node (ref "C6") (pin "1") (pinfunction "1_1") (pintype "passive"))
      (node (ref "R4") (pin "2") (pinfunction "2_2") (pintype "passive"))
    )
    (net (code "71") (name "Net-(D1-K)") (class "Default")
      (node (ref "D1") (pin "2") (pinfunction "K_2") (pintype "passive"))
      (node (ref "D2") (pin "2") (pinfunction "K_2") (pintype "passive"))
      (node (ref "SP1") (pin "2") (pinfunction "2_2") (pintype "passive"))
    )
    (net (code "72") (name "Net-(D2-A)") (class "Default")
      (node (ref "D2") (pin "1") (pinfunction "A_1") (pintype "passive"))
      (node (ref "J1") (pin "2") (pintype "passive"))
    )
    (net (code "73") (name "Net-(D3-A)") (class "Default")
      (node (ref "D3") (pin "1") (pinfunction "A_1") (pintype "passive"))
      (node (ref "Q1") (pin "3") (pinfunction "D_3") (pintype "passive"))
      (node (ref "V1") (pin "2") (pintype "passive"))
    )
    (net (code "74") (name "Net-(F1-P1)") (class "Default")
      (node (ref "F1") (pin "1") (pinfunction "P1_1") (pintype "passive"))
      (node (ref "SP1") (pin "3") (pinfunction "3_3") (pintype "passive"))
    )
    (net (code "75") (name "Net-(J2-G-)") (class "Default")
      (node (ref "J2") (pin "10") (pinfunction "G-_10") (pintype "passive"))
      (node (ref "R14") (pin "1") (pinfunction "1_1") (pintype "passive"))
    )
    (net (code "76") (name "Net-(J2-Y-)") (class "Default")
      (node (ref "J2") (pin "11") (pinfunction "Y-_11") (pintype "passive"))
      (node (ref "R16") (pin "1") (pinfunction "1_1") (pintype "passive"))
    )
    (net (code "77") (name "Net-(LED1-A)") (class "Default")
      (node (ref "LED1") (pin "1") (pinfunction "A_1") (pintype "passive"))
      (node (ref "R26") (pin "2") (pinfunction "2_2") (pintype "passive"))
    )
    (net (code "78") (name "Net-(LED2-A)") (class "Default")
      (node (ref "LED2") (pin "1") (pinfunction "A_1") (pintype "passive"))
      (node (ref "R27") (pin "2") (pinfunction "2_2") (pintype "passive"))
    )
    (net (code "79") (name "Net-(LED3-A)") (class "Default")
      (node (ref "LED3") (pin "1") (pinfunction "A_1") (pintype "passive"))
      (node (ref "R28") (pin "2") (pinfunction "2_2") (pintype "passive"))
    )
    (net (code "80") (name "Net-(Q1-G)") (class "Default")
      (node (ref "Q1") (pin "1") (pinfunction "G_1") (pintype "passive"))
      (node (ref "R30") (pin "2") (pinfunction "2_2") (pintype "passive"))
    )
    (net (code "81") (name "Net-(R22-Pad2)") (class "Default")
      (node (ref "R22") (pin "2") (pinfunction "2_2") (pintype "passive"))
      (node (ref "R23") (pin "1") (pinfunction "1_1") (pintype "passive"))
      (node (ref "Y1") (pin "3") (pintype "passive"))
    )
    (net (code "82") (name "Net-(U2-BYPASS)") (class "Default")
      (node (ref "C3") (pin "2") (pinfunction "2_2") (pintype "passive"))
      (node (ref "U2") (pin "2") (pinfunction "BYPASS_2") (pintype "passive"))
      (node (ref "U2") (pin "3") (pinfunction "INP_3") (pintype "passive"))
    )
    (net (code "83") (name "Net-(U2-INM)") (class "Default")
      (node (ref "R2") (pin "2") (pinfunction "2_2") (pintype "passive"))
      (node (ref "R4") (pin "1") (pinfunction "1_1") (pintype "passive"))
      (node (ref "U2") (pin "4") (pinfunction "INM_4") (pintype "passive"))
    )
    (net (code "84") (name "Net-(U2-SHUTDOWN)") (class "Default")
      (node (ref "R1") (pin "2") (pinfunction "2_2") (pintype "passive"))
      (node (ref "U2") (pin "1") (pinfunction "SHUTDOWN_1") (pintype "passive"))
    )
    (net (code "85") (name "Net-(U6-CRS_DV{slash}MODE2)") (class "Default")
      (node (ref "R20") (pin "2") (pinfunction "2_2") (pintype "passive"))
      (node (ref "U6") (pin "11") (pinfunction "CRS_DV/MODE2_11") (pintype "passive"))
    )
    (net (code "86") (name "Net-(U6-RBIAS)") (class "Default")
      (node (ref "R24") (pin "2") (pinfunction "2_2") (pintype "passive"))
      (node (ref "U6") (pin "24") (pinfunction "RBIAS_24") (pintype "passive"))
    )
    (net (code "87") (name "Net-(U6-RXD0{slash}MODE0)") (class "Default")
      (node (ref "R12") (pin "2") (pinfunction "2_2") (pintype "passive"))
      (node (ref "U6") (pin "8") (pinfunction "RXD0/MODE0_8") (pintype "passive"))
    )
    (net (code "88") (name "Net-(U6-RXD1{slash}MODE1)") (class "Default")
      (node (ref "R10") (pin "2") (pinfunction "2_2") (pintype "passive"))
      (node (ref "U6") (pin "7") (pinfunction "RXD1/MODE1_7") (pintype "passive"))
    )
    (net (code "89") (name "Net-(U6-RXER{slash}PHYAD0)") (class "Default")
      (node (ref "R19") (pin "2") (pinfunction "2_2") (pintype "passive"))
      (node (ref "U6") (pin "10") (pinfunction "RXER/PHYAD0_10") (pintype "passive"))
    )
    (net (code "90") (name "Net-(U6-VDDCR)") (class "Default")
      (node (ref "C12") (pin "1") (pinfunction "1_1") (pintype "passive"))
      (node (ref "C13") (pin "1") (pinfunction "1_1") (pintype "passive"))
      (node (ref "U6") (pin "6") (pinfunction "VDDCR_6") (pintype "passive"))
    )
    (net (code "91") (name "Net-(U6-XTAL1{slash}CLKIN)") (class "Default")
      (node (ref "R23") (pin "2") (pinfunction "2_2") (pintype "passive"))
      (node (ref "U6") (pin "5") (pinfunction "XTAL1/CLKIN_5") (pintype "passive"))
    )
    (net (code "92") (name "Net-(U6-nINT{slash}REFCLKO)") (class "Default")
      (node (ref "R21") (pin "2") (pinfunction "2_2") (pintype "passive"))
      (node (ref "U6") (pin "14") (pinfunction "nINT/REFCLKO_14") (pintype "passive"))
    )
    (net (code "93") (name "Net-(U7-RS)") (class "Default")
      (node (ref "R18") (pin "2") (pinfunction "2_2") (pintype "passive"))
      (node (ref "U7") (pin "8") (pinfunction "RS_8") (pintype "passive"))
    )
    (net (code "94") (name "VDDA") (class "Default")
      (node (ref "C8") (pin "2") (pinfunction "2_2") (pintype "passive"))
      (node (ref "C9") (pin "2") (pinfunction "2_2") (pintype "passive"))
      (node (ref "L1") (pin "1") (pinfunction "1_1") (pintype "passive"))
      (node (ref "U6") (pin "1") (pinfunction "VDD2A_1") (pintype "passive"))
      (node (ref "U6") (pin "19") (pinfunction "VDD1A_19") (pintype "passive"))
    )
    (net (code "95") (name "unconnected-(J3-Pad4)") (class "Default")
      (node (ref "J3") (pin "4") (pinfunction "4_4") (pintype "passive+no_connect"))
    )
    (net (code "96") (name "unconnected-(J4-Pad3)") (class "Default")
      (node (ref "J4") (pin "3") (pinfunction "3_3") (pintype "passive+no_connect"))
    )
    (net (code "97") (name "unconnected-(J5-Pad3)") (class "Default")
      (node (ref "J5") (pin "3") (pinfunction "3_3") (pintype "passive+no_connect"))
    )
    (net (code "98") (name "unconnected-(P2-Pad10)") (class "Default")
      (node (ref "P2") (pin "10") (pinfunction "10_10") (pintype "passive+no_connect"))
    )
    (net (code "99") (name "unconnected-(P2-Pad12)") (class "Default")
      (node (ref "P2") (pin "12") (pinfunction "12_12") (pintype "passive+no_connect"))
    )
    (net (code "100") (name "unconnected-(P2-Pad23)") (class "Default")
      (node (ref "P2") (pin "23") (pinfunction "23_23") (pintype "passive+no_connect"))
    )
    (net (code "101") (name "unconnected-(SP1-Pad1)") (class "Default")
      (node (ref "SP1") (pin "1") (pinfunction "1_1") (pintype "passive"))
    )
    (net (code "102") (name "unconnected-(U6-XTAL2-Pad4)") (class "Default")
      (node (ref "U6") (pin "4") (pinfunction "XTAL2_4") (pintype "passive+no_connect"))
    )
    (net (code "103") (name "unconnected-(U7-Vref-Pad5)") (class "Default")
      (node (ref "U7") (pin "5") (pinfunction "Vref_5") (pintype "passive+no_connect"))
    )
    (net (code "104") (name "unconnected-(V1-NC-Pad3)") (class "Default")
      (node (ref "V1") (pin "3") (pinfunction "NC_3") (pintype "passive"))
    )
  )
)
